# r10_0_328_1284.net
KiCad netlist of a schematic drawn in EAGLE
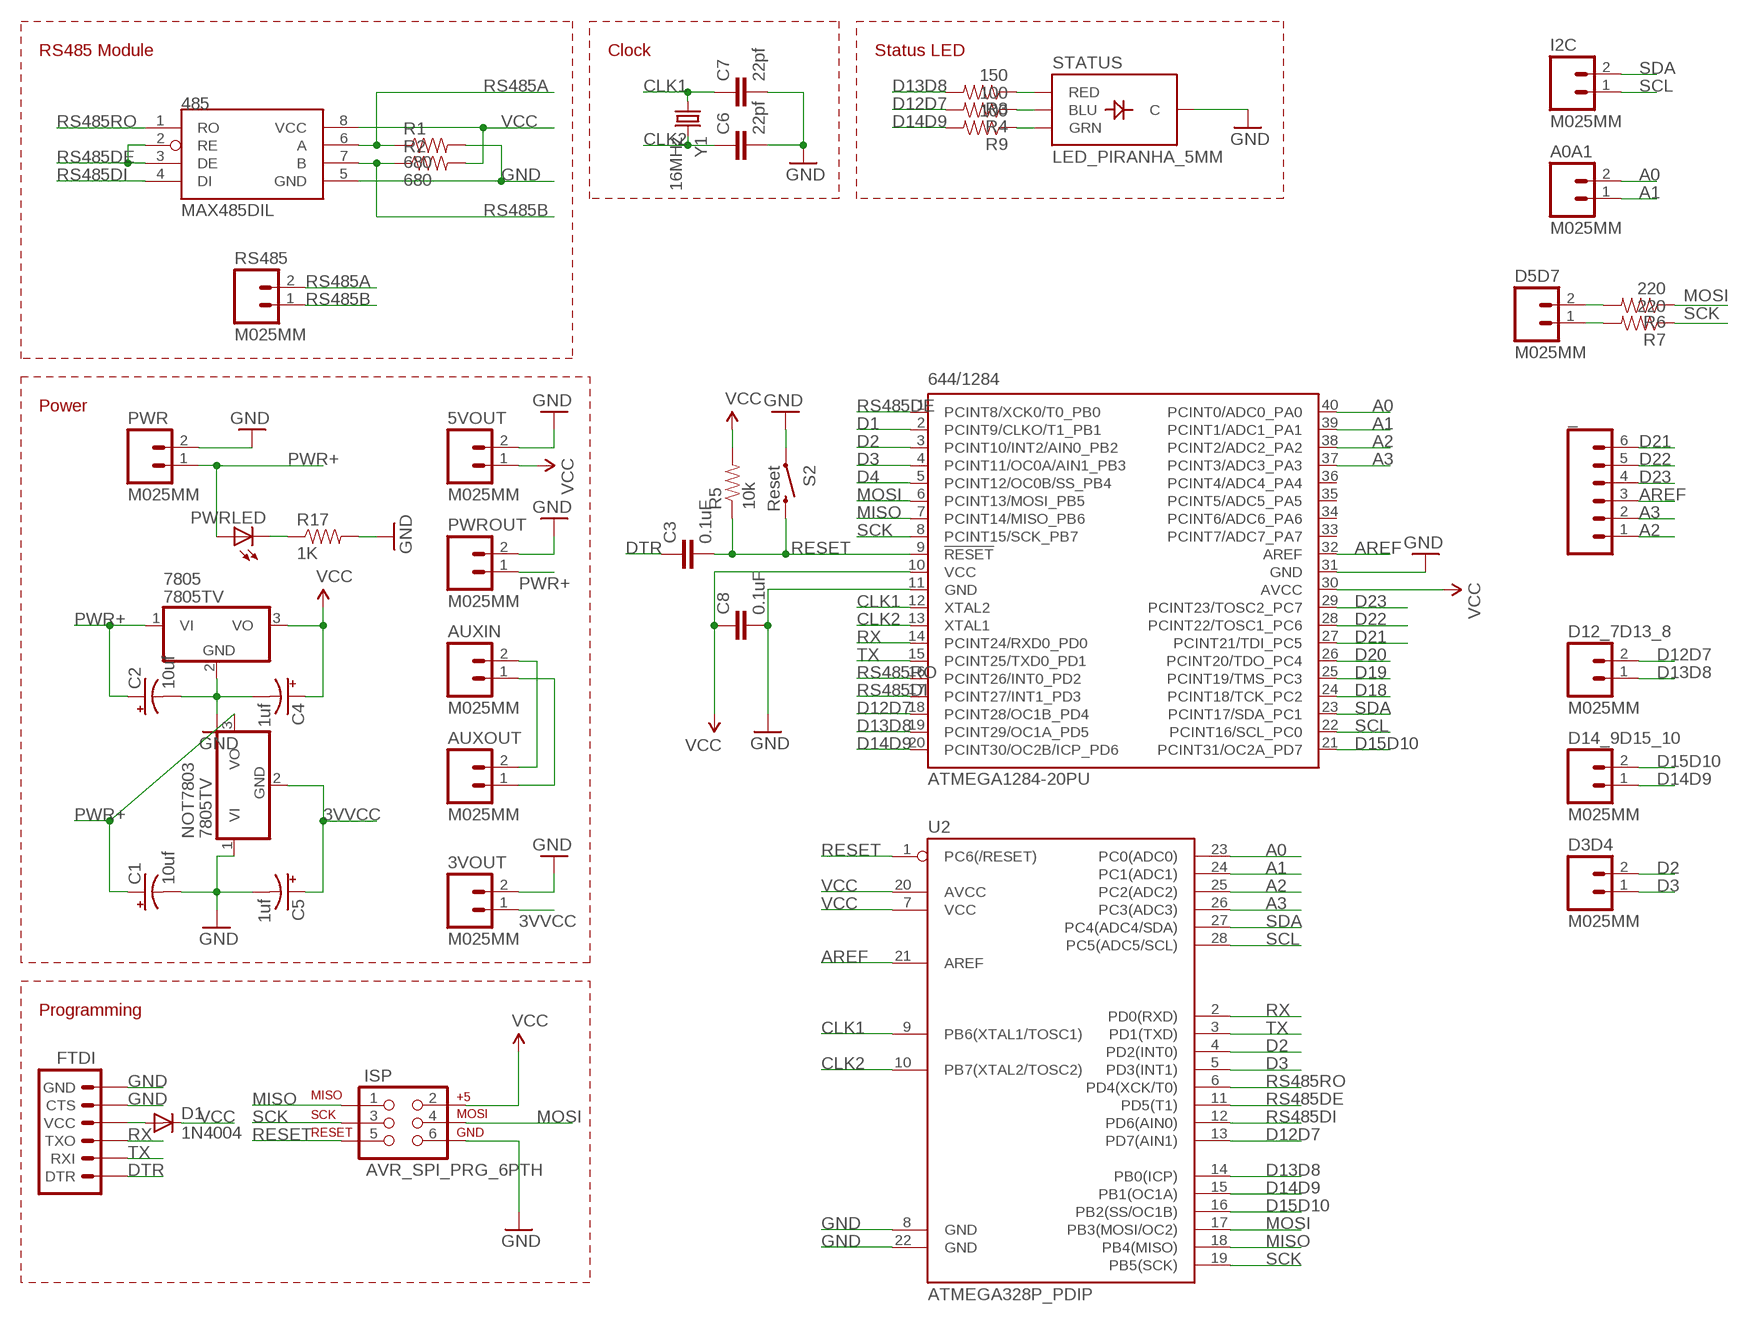
[diagram p0: schematic, sheet 1]

(export (version "E")
  (design (tool "Eeschema 10.0.6"))
  (components
    (comp (ref "3VOUT")
      (value "M025MM")
      (footprint "eagle-import:SCREWTERMINAL-5MM-2")
      (libsource (lib "eagle-import") (part "M025MM"))
    )
    (comp (ref "5VOUT")
      (value "M025MM")
      (footprint "eagle-import:SCREWTERMINAL-5MM-2")
      (libsource (lib "eagle-import") (part "M025MM"))
    )
    (comp (ref "485")
      (value "MAX485DIL")
      (footprint "eagle-import:DIL08")
      (libsource (lib "eagle-import") (part "MAX485DIL"))
    )
    (comp (ref "644/1284")
      (value "ATMEGA1284-20PU")
      (footprint "eagle-import:DIL40")
      (fields (field (name "MPN") "ATMEGA644-20PU"))
      (libsource (lib "eagle-import") (part "ATMEGA644-PU20"))
    )
    (comp (ref "7805")
      (value "7805TV")
      (footprint "eagle-import:TO220V")
      (libsource (lib "eagle-import") (part "78TV05"))
    )
    (comp (ref "A0A1")
      (value "M025MM")
      (footprint "eagle-import:SCREWTERMINAL-5MM-2")
      (libsource (lib "eagle-import") (part "M025MM"))
    )
    (comp (ref "AUXIN")
      (value "M025MM")
      (footprint "eagle-import:SCREWTERMINAL-5MM-2")
      (libsource (lib "eagle-import") (part "M025MM"))
    )
    (comp (ref "AUXOUT")
      (value "M025MM")
      (footprint "eagle-import:SCREWTERMINAL-5MM-2")
      (libsource (lib "eagle-import") (part "M025MM"))
    )
    (comp (ref "C1")
      (value "10uf")
      (footprint "eagle-import:CPOL-RADIAL-10UF-25V")
      (libsource (lib "eagle-import") (part "CAP_POLPTH2"))
    )
    (comp (ref "C2")
      (value "10uf")
      (footprint "eagle-import:CPOL-RADIAL-10UF-25V")
      (libsource (lib "eagle-import") (part "CAP_POLPTH2"))
    )
    (comp (ref "C3")
      (value "0.1uF")
      (footprint "eagle-import:CAP-PTH-SMALL")
      (libsource (lib "eagle-import") (part "CAPPTH"))
    )
    (comp (ref "C4")
      (value "1uf")
      (footprint "eagle-import:CPOL-RADIAL-10UF-25V")
      (libsource (lib "eagle-import") (part "CAP_POLPTH2"))
    )
    (comp (ref "C5")
      (value "1uf")
      (footprint "eagle-import:CPOL-RADIAL-10UF-25V")
      (libsource (lib "eagle-import") (part "CAP_POLPTH2"))
    )
    (comp (ref "C6")
      (value "22pf")
      (footprint "eagle-import:CAP-PTH-SMALL")
      (libsource (lib "eagle-import") (part "CAPPTH"))
    )
    (comp (ref "C7")
      (value "22pf")
      (footprint "eagle-import:CAP-PTH-SMALL")
      (libsource (lib "eagle-import") (part "CAPPTH"))
    )
    (comp (ref "C8")
      (value "0.1uF")
      (footprint "eagle-import:CAP-PTH-SMALL")
      (libsource (lib "eagle-import") (part "CAPPTH"))
    )
    (comp (ref "D1")
      (value "1N4004")
      (footprint "eagle-import:DO41-10")
      (libsource (lib "eagle-import") (part "1N4004"))
    )
    (comp (ref "D3D4")
      (value "M025MM")
      (footprint "eagle-import:SCREWTERMINAL-5MM-2")
      (libsource (lib "eagle-import") (part "M025MM"))
    )
    (comp (ref "D5D7")
      (value "M025MM")
      (footprint "eagle-import:SCREWTERMINAL-5MM-2")
      (libsource (lib "eagle-import") (part "M025MM"))
    )
    (comp (ref "D12_7D13_8")
      (value "M025MM")
      (footprint "eagle-import:SCREWTERMINAL-5MM-2")
      (libsource (lib "eagle-import") (part "M025MM"))
    )
    (comp (ref "D14_9D15_10")
      (value "M025MM")
      (footprint "eagle-import:SCREWTERMINAL-5MM-2")
      (libsource (lib "eagle-import") (part "M025MM"))
    )
    (comp (ref "FTDI")
      (value "ARDUINO_SERIAL_PROGRAMPTH")
      (footprint "eagle-import:1X06")
      (libsource (lib "eagle-import") (part "ARDUINO_SERIAL_PROGRAMPTH"))
    )
    (comp (ref "I2C")
      (value "M025MM")
      (footprint "eagle-import:SCREWTERMINAL-5MM-2")
      (libsource (lib "eagle-import") (part "M025MM"))
    )
    (comp (ref "ISP")
      (value "AVR_SPI_PRG_6PTH")
      (footprint "eagle-import:2X3")
      (libsource (lib "eagle-import") (part "AVR_SPI_PRG_6PTH"))
    )
    (comp (ref "NOT7803")
      (value "7805TV")
      (footprint "eagle-import:TO220V")
      (libsource (lib "eagle-import") (part "78TV05"))
    )
    (comp (ref "PWR")
      (value "M025MM")
      (footprint "eagle-import:SCREWTERMINAL-5MM-2")
      (libsource (lib "eagle-import") (part "M025MM"))
    )
    (comp (ref "PWRLED")
      (value "LED5MM")
      (footprint "eagle-import:LED5MM")
      (libsource (lib "eagle-import") (part "LED5MM"))
    )
    (comp (ref "PWROUT")
      (value "M025MM")
      (footprint "eagle-import:SCREWTERMINAL-5MM-2")
      (libsource (lib "eagle-import") (part "M025MM"))
    )
    (comp (ref "R1")
      (value "680")
      (footprint "eagle-import:AXIAL-0.4")
      (libsource (lib "eagle-import") (part "SparkFun-Resistors_RESISTORPTH-1/4W"))
    )
    (comp (ref "R2")
      (value "680")
      (footprint "eagle-import:AXIAL-0.4")
      (libsource (lib "eagle-import") (part "SparkFun-Resistors_RESISTORPTH-1/4W"))
    )
    (comp (ref "R3")
      (value "150")
      (footprint "eagle-import:AXIAL-0.4")
      (libsource (lib "eagle-import") (part "RESISTORPTH-1/4W"))
    )
    (comp (ref "R4")
      (value "100")
      (footprint "eagle-import:AXIAL-0.4")
      (libsource (lib "eagle-import") (part "RESISTORPTH-1/4W"))
    )
    (comp (ref "R5")
      (value "10k")
      (footprint "eagle-import:AXIAL-0.4")
      (libsource (lib "eagle-import") (part "RESISTORPTH-1/4W"))
    )
    (comp (ref "R6")
      (value "220")
      (footprint "eagle-import:AXIAL-0.4")
      (libsource (lib "eagle-import") (part "RESISTORPTH-1/4W"))
    )
    (comp (ref "R7")
      (value "220")
      (footprint "eagle-import:AXIAL-0.4")
      (libsource (lib "eagle-import") (part "RESISTORPTH-1/4W"))
    )
    (comp (ref "R9")
      (value "100")
      (footprint "eagle-import:AXIAL-0.4")
      (libsource (lib "eagle-import") (part "RESISTORPTH-1/4W"))
    )
    (comp (ref "R17")
      (value "1K")
      (footprint "eagle-import:AXIAL-0.4")
      (libsource (lib "eagle-import") (part "SparkFun-Resistors_RESISTORPTH-1/4W"))
    )
    (comp (ref "RS485")
      (value "M025MM")
      (footprint "eagle-import:SCREWTERMINAL-5MM-2")
      (libsource (lib "eagle-import") (part "M025MM"))
    )
    (comp (ref "S2")
      (value "Reset")
      (footprint "eagle-import:TACTILE_SWITCH_SMD")
      (libsource (lib "eagle-import") (part "SWITCH-MOMENTARY-2SMD"))
    )
    (comp (ref "STATUS")
      (value "LED_PIRANHA_5MM")
      (footprint "eagle-import:LED_PIRANHA_5MM")
      (libsource (lib "eagle-import") (part "LED_PIRANHA_5MM"))
    )
    (comp (ref "U2")
      (value "ATMEGA328P_PDIP")
      (footprint "eagle-import:DIL28-3")
      (libsource (lib "eagle-import") (part "ATMEGA328P_PDIP"))
    )
    (comp (ref "Y1")
      (value "16MHz")
      (footprint "eagle-import:HC49US")
      (libsource (lib "eagle-import") (part "CRYSTALHC49US"))
    )
    (comp (ref "_")
      (value "M06NO_SILK")
      (footprint "eagle-import:1X06_NO_SILK")
      (libsource (lib "eagle-import") (part "M06NO_SILK"))
    )
  )
  (nets
    (net (code "1") (name "/3VVCC") (class "Default")
      (node (ref "3VOUT") (pin "1") (pinfunction "1_1") (pintype "passive"))
      (node (ref "C5") (pin "1") (pinfunction "+_1") (pintype "passive"))
      (node (ref "NOT7803") (pin "2") (pinfunction "GND_2") (pintype "passive"))
    )
    (net (code "2") (name "/A0") (class "Default")
      (node (ref "644/1284") (pin "40") (pinfunction "PCINT0/ADC0_PA0_40") (pintype "bidirectional"))
      (node (ref "A0A1") (pin "2") (pinfunction "2_2") (pintype "passive"))
      (node (ref "U2") (pin "23") (pinfunction "PC0(ADC0)_23") (pintype "bidirectional"))
    )
    (net (code "3") (name "/A1") (class "Default")
      (node (ref "644/1284") (pin "39") (pinfunction "PCINT1/ADC1_PA1_39") (pintype "bidirectional"))
      (node (ref "A0A1") (pin "1") (pinfunction "1_1") (pintype "passive"))
      (node (ref "U2") (pin "24") (pinfunction "PC1(ADC1)_24") (pintype "bidirectional"))
    )
    (net (code "4") (name "/A2") (class "Default")
      (node (ref "644/1284") (pin "38") (pinfunction "PCINT2/ADC2_PA2_38") (pintype "bidirectional"))
      (node (ref "U2") (pin "25") (pinfunction "PC2(ADC2)_25") (pintype "bidirectional"))
      (node (ref "_") (pin "1") (pinfunction "1_1") (pintype "passive"))
    )
    (net (code "5") (name "/A3") (class "Default")
      (node (ref "644/1284") (pin "37") (pinfunction "PCINT3/ADC3_PA3_37") (pintype "bidirectional"))
      (node (ref "U2") (pin "26") (pinfunction "PC3(ADC3)_26") (pintype "bidirectional"))
      (node (ref "_") (pin "2") (pinfunction "2_2") (pintype "passive"))
    )
    (net (code "6") (name "/AREF") (class "Default")
      (node (ref "644/1284") (pin "32") (pinfunction "AREF_32") (pintype "passive"))
      (node (ref "U2") (pin "21") (pinfunction "AREF_21") (pintype "bidirectional"))
      (node (ref "_") (pin "3") (pinfunction "3_3") (pintype "passive"))
    )
    (net (code "7") (name "/CLK1") (class "Default")
      (node (ref "644/1284") (pin "12") (pinfunction "XTAL2_12") (pintype "output"))
      (node (ref "C7") (pin "1") (pinfunction "1_1") (pintype "passive"))
      (node (ref "U2") (pin "9") (pinfunction "PB6(XTAL1/TOSC1)_9") (pintype "bidirectional"))
      (node (ref "Y1") (pin "1") (pinfunction "1_1") (pintype "passive"))
    )
    (net (code "8") (name "/CLK2") (class "Default")
      (node (ref "644/1284") (pin "13") (pinfunction "XTAL1_13") (pintype "input"))
      (node (ref "C6") (pin "1") (pinfunction "1_1") (pintype "passive"))
      (node (ref "U2") (pin "10") (pinfunction "PB7(XTAL2/TOSC2)_10") (pintype "bidirectional"))
      (node (ref "Y1") (pin "2") (pinfunction "2_2") (pintype "passive"))
    )
    (net (code "9") (name "/D1") (class "Default")
      (node (ref "644/1284") (pin "2") (pinfunction "PCINT9/CLKO/T1_PB1_2") (pintype "bidirectional"))
    )
    (net (code "10") (name "/D2") (class "Default")
      (node (ref "644/1284") (pin "3") (pinfunction "PCINT10/INT2/AIN0_PB2_3") (pintype "bidirectional"))
      (node (ref "D3D4") (pin "2") (pinfunction "2_2") (pintype "passive"))
      (node (ref "U2") (pin "4") (pinfunction "PD2(INT0)_4") (pintype "bidirectional"))
    )
    (net (code "11") (name "/D3") (class "Default")
      (node (ref "644/1284") (pin "4") (pinfunction "PCINT11/OC0A/AIN1_PB3_4") (pintype "bidirectional"))
      (node (ref "D3D4") (pin "1") (pinfunction "1_1") (pintype "passive"))
      (node (ref "U2") (pin "5") (pinfunction "PD3(INT1)_5") (pintype "bidirectional"))
    )
    (net (code "12") (name "/D4") (class "Default")
      (node (ref "644/1284") (pin "5") (pinfunction "PCINT12/OC0B/SS_PB4_5") (pintype "bidirectional"))
    )
    (net (code "13") (name "/D12D7") (class "Default")
      (node (ref "644/1284") (pin "18") (pinfunction "PCINT28/OC1B_PD4_18") (pintype "bidirectional"))
      (node (ref "D12_7D13_8") (pin "2") (pinfunction "2_2") (pintype "passive"))
      (node (ref "R4") (pin "P$2") (pinfunction "2_P$2") (pintype "passive"))
      (node (ref "U2") (pin "13") (pinfunction "PD7(AIN1)_13") (pintype "bidirectional"))
    )
    (net (code "14") (name "/D13D8") (class "Default")
      (node (ref "644/1284") (pin "19") (pinfunction "PCINT29/OC1A_PD5_19") (pintype "bidirectional"))
      (node (ref "D12_7D13_8") (pin "1") (pinfunction "1_1") (pintype "passive"))
      (node (ref "R3") (pin "P$2") (pinfunction "2_P$2") (pintype "passive"))
      (node (ref "U2") (pin "14") (pinfunction "PB0(ICP)_14") (pintype "bidirectional"))
    )
    (net (code "15") (name "/D14D9") (class "Default")
      (node (ref "644/1284") (pin "20") (pinfunction "PCINT30/OC2B/ICP_PD6_20") (pintype "bidirectional"))
      (node (ref "D14_9D15_10") (pin "1") (pinfunction "1_1") (pintype "passive"))
      (node (ref "R9") (pin "P$2") (pinfunction "2_P$2") (pintype "passive"))
      (node (ref "U2") (pin "15") (pinfunction "PB1(OC1A)_15") (pintype "bidirectional"))
    )
    (net (code "16") (name "/D15D10") (class "Default")
      (node (ref "644/1284") (pin "21") (pinfunction "PCINT31/OC2A_PD7_21") (pintype "bidirectional"))
      (node (ref "D14_9D15_10") (pin "2") (pinfunction "2_2") (pintype "passive"))
      (node (ref "U2") (pin "16") (pinfunction "PB2(SS/OC1B)_16") (pintype "bidirectional"))
    )
    (net (code "17") (name "/D18") (class "Default")
      (node (ref "644/1284") (pin "24") (pinfunction "PCINT18/TCK_PC2_24") (pintype "bidirectional"))
    )
    (net (code "18") (name "/D19") (class "Default")
      (node (ref "644/1284") (pin "25") (pinfunction "PCINT19/TMS_PC3_25") (pintype "bidirectional"))
    )
    (net (code "19") (name "/D20") (class "Default")
      (node (ref "644/1284") (pin "26") (pinfunction "PCINT20/TDO_PC4_26") (pintype "bidirectional"))
    )
    (net (code "20") (name "/D21") (class "Default")
      (node (ref "644/1284") (pin "27") (pinfunction "PCINT21/TDI_PC5_27") (pintype "bidirectional"))
      (node (ref "_") (pin "6") (pinfunction "6_6") (pintype "passive"))
    )
    (net (code "21") (name "/D22") (class "Default")
      (node (ref "644/1284") (pin "28") (pinfunction "PCINT22/TOSC1_PC6_28") (pintype "bidirectional"))
      (node (ref "_") (pin "5") (pinfunction "5_5") (pintype "passive"))
    )
    (net (code "22") (name "/D23") (class "Default")
      (node (ref "644/1284") (pin "29") (pinfunction "PCINT23/TOSC2_PC7_29") (pintype "bidirectional"))
      (node (ref "_") (pin "4") (pinfunction "4_4") (pintype "passive"))
    )
    (net (code "23") (name "/DTR") (class "Default")
      (node (ref "C3") (pin "1") (pinfunction "1_1") (pintype "passive"))
      (node (ref "FTDI") (pin "DTR") (pinfunction "DTR_DTR") (pintype "passive"))
    )
    (net (code "24") (name "/MISO") (class "Default")
      (node (ref "644/1284") (pin "7") (pinfunction "PCINT14/MISO_PB6_7") (pintype "bidirectional"))
      (node (ref "ISP") (pin "1") (pinfunction "1_1") (pintype "passive"))
      (node (ref "U2") (pin "18") (pinfunction "PB4(MISO)_18") (pintype "bidirectional"))
    )
    (net (code "25") (name "/MOSI") (class "Default")
      (node (ref "644/1284") (pin "6") (pinfunction "PCINT13/MOSI_PB5_6") (pintype "bidirectional"))
      (node (ref "ISP") (pin "4") (pinfunction "4_4") (pintype "passive"))
      (node (ref "R6") (pin "P$1") (pinfunction "1_P$1") (pintype "passive"))
      (node (ref "U2") (pin "17") (pinfunction "PB3(MOSI/OC2)_17") (pintype "bidirectional"))
    )
    (net (code "26") (name "/PWR+") (class "Default")
      (node (ref "7805") (pin "1") (pinfunction "VI_1") (pintype "input"))
      (node (ref "C1") (pin "1") (pinfunction "+_1") (pintype "passive"))
      (node (ref "C2") (pin "1") (pinfunction "+_1") (pintype "passive"))
      (node (ref "NOT7803") (pin "3") (pinfunction "VO_3") (pintype "passive"))
      (node (ref "PWR") (pin "1") (pinfunction "1_1") (pintype "passive"))
      (node (ref "PWRLED") (pin "A") (pinfunction "A_A") (pintype "passive"))
      (node (ref "PWROUT") (pin "1") (pinfunction "1_1") (pintype "passive"))
    )
    (net (code "27") (name "/RESET") (class "Default")
      (node (ref "644/1284") (pin "9") (pinfunction "~{RESET}_9") (pintype "input"))
      (node (ref "C3") (pin "2") (pinfunction "2_2") (pintype "passive"))
      (node (ref "ISP") (pin "5") (pinfunction "5_5") (pintype "passive"))
      (node (ref "R5") (pin "P$1") (pinfunction "1_P$1") (pintype "passive"))
      (node (ref "S2") (pin "3") (pinfunction "2_3") (pintype "passive"))
      (node (ref "U2") (pin "1") (pinfunction "PC6(/RESET)_1") (pintype "bidirectional"))
    )
    (net (code "28") (name "/RS485A") (class "Default")
      (node (ref "485") (pin "6") (pinfunction "A_6") (pintype "bidirectional"))
      (node (ref "R1") (pin "P$1") (pinfunction "1_P$1") (pintype "passive"))
      (node (ref "RS485") (pin "2") (pinfunction "2_2") (pintype "passive"))
    )
    (net (code "29") (name "/RS485B") (class "Default")
      (node (ref "485") (pin "7") (pinfunction "B_7") (pintype "bidirectional"))
      (node (ref "R2") (pin "P$1") (pinfunction "1_P$1") (pintype "passive"))
      (node (ref "RS485") (pin "1") (pinfunction "1_1") (pintype "passive"))
    )
    (net (code "30") (name "/RS485DE") (class "Default")
      (node (ref "485") (pin "2") (pinfunction "RE_2") (pintype "bidirectional"))
      (node (ref "485") (pin "3") (pinfunction "DE_3") (pintype "bidirectional"))
      (node (ref "644/1284") (pin "1") (pinfunction "PCINT8/XCK0/T0_PB0_1") (pintype "bidirectional"))
      (node (ref "U2") (pin "11") (pinfunction "PD5(T1)_11") (pintype "bidirectional"))
    )
    (net (code "31") (name "/RS485DI") (class "Default")
      (node (ref "485") (pin "4") (pinfunction "DI_4") (pintype "bidirectional"))
      (node (ref "644/1284") (pin "17") (pinfunction "PCINT27/INT1_PD3_17") (pintype "bidirectional"))
      (node (ref "U2") (pin "12") (pinfunction "PD6(AIN0)_12") (pintype "bidirectional"))
    )
    (net (code "32") (name "/RS485RO") (class "Default")
      (node (ref "485") (pin "1") (pinfunction "RO_1") (pintype "bidirectional"))
      (node (ref "644/1284") (pin "16") (pinfunction "PCINT26/INT0_PD2_16") (pintype "bidirectional"))
      (node (ref "U2") (pin "6") (pinfunction "PD4(XCK/T0)_6") (pintype "bidirectional"))
    )
    (net (code "33") (name "/RX") (class "Default")
      (node (ref "644/1284") (pin "14") (pinfunction "PCINT24/RXD0_PD0_14") (pintype "bidirectional"))
      (node (ref "FTDI") (pin "TXO") (pinfunction "TXO_TXO") (pintype "passive"))
      (node (ref "U2") (pin "2") (pinfunction "PD0(RXD)_2") (pintype "bidirectional"))
    )
    (net (code "34") (name "/SCK") (class "Default")
      (node (ref "644/1284") (pin "8") (pinfunction "PCINT15/SCK_PB7_8") (pintype "bidirectional"))
      (node (ref "ISP") (pin "3") (pinfunction "3_3") (pintype "passive"))
      (node (ref "R7") (pin "P$1") (pinfunction "1_P$1") (pintype "passive"))
      (node (ref "U2") (pin "19") (pinfunction "PB5(SCK)_19") (pintype "bidirectional"))
    )
    (net (code "35") (name "/SCL") (class "Default")
      (node (ref "644/1284") (pin "22") (pinfunction "PCINT16/SCL_PC0_22") (pintype "bidirectional"))
      (node (ref "I2C") (pin "1") (pinfunction "1_1") (pintype "passive"))
      (node (ref "U2") (pin "28") (pinfunction "PC5(ADC5/SCL)_28") (pintype "bidirectional"))
    )
    (net (code "36") (name "/SDA") (class "Default")
      (node (ref "644/1284") (pin "23") (pinfunction "PCINT17/SDA_PC1_23") (pintype "bidirectional"))
      (node (ref "I2C") (pin "2") (pinfunction "2_2") (pintype "passive"))
      (node (ref "U2") (pin "27") (pinfunction "PC4(ADC4/SDA)_27") (pintype "bidirectional"))
    )
    (net (code "37") (name "/TX") (class "Default")
      (node (ref "644/1284") (pin "15") (pinfunction "PCINT25/TXD0_PD1_15") (pintype "bidirectional"))
      (node (ref "FTDI") (pin "RXI") (pinfunction "RXI_RXI") (pintype "passive"))
      (node (ref "U2") (pin "3") (pinfunction "PD1(TXD)_3") (pintype "bidirectional"))
    )
    (net (code "38") (name "GND") (class "Default")
      (node (ref "3VOUT") (pin "2") (pinfunction "2_2") (pintype "passive"))
      (node (ref "485") (pin "5") (pinfunction "GND_5") (pintype "bidirectional"))
      (node (ref "5VOUT") (pin "2") (pinfunction "2_2") (pintype "passive"))
      (node (ref "644/1284") (pin "11") (pinfunction "GND_11") (pintype "power_in"))
      (node (ref "644/1284") (pin "31") (pinfunction "GND_31") (pintype "power_in"))
      (node (ref "7805") (pin "2") (pinfunction "GND_2") (pintype "passive"))
      (node (ref "C1") (pin "2") (pinfunction "-_2") (pintype "passive"))
      (node (ref "C2") (pin "2") (pinfunction "-_2") (pintype "passive"))
      (node (ref "C4") (pin "2") (pinfunction "-_2") (pintype "passive"))
      (node (ref "C5") (pin "2") (pinfunction "-_2") (pintype "passive"))
      (node (ref "C6") (pin "2") (pinfunction "2_2") (pintype "passive"))
      (node (ref "C7") (pin "2") (pinfunction "2_2") (pintype "passive"))
      (node (ref "C8") (pin "2") (pinfunction "2_2") (pintype "passive"))
      (node (ref "FTDI") (pin "CTS") (pinfunction "CTS_CTS") (pintype "passive"))
      (node (ref "FTDI") (pin "GND") (pinfunction "GND_GND") (pintype "passive"))
      (node (ref "ISP") (pin "6") (pinfunction "6_6") (pintype "passive"))
      (node (ref "NOT7803") (pin "1") (pinfunction "VI_1") (pintype "input"))
      (node (ref "PWR") (pin "2") (pinfunction "2_2") (pintype "passive"))
      (node (ref "PWROUT") (pin "2") (pinfunction "2_2") (pintype "passive"))
      (node (ref "R1") (pin "P$2") (pinfunction "2_P$2") (pintype "passive"))
      (node (ref "R17") (pin "P$2") (pinfunction "2_P$2") (pintype "passive"))
      (node (ref "S2") (pin "1") (pinfunction "1_1") (pintype "passive"))
      (node (ref "STATUS") (pin "-") (pinfunction "C_-") (pintype "bidirectional"))
      (node (ref "U2") (pin "22") (pinfunction "GND_22") (pintype "bidirectional"))
      (node (ref "U2") (pin "8") (pinfunction "GND_8") (pintype "bidirectional"))
    )
    (net (code "39") (name "Net-(AUXIN-Pad1)") (class "Default")
      (node (ref "AUXIN") (pin "1") (pinfunction "1_1") (pintype "passive"))
      (node (ref "AUXOUT") (pin "1") (pinfunction "1_1") (pintype "passive"))
    )
    (net (code "40") (name "Net-(AUXIN-Pad2)") (class "Default")
      (node (ref "AUXIN") (pin "2") (pinfunction "2_2") (pintype "passive"))
      (node (ref "AUXOUT") (pin "2") (pinfunction "2_2") (pintype "passive"))
    )
    (net (code "41") (name "Net-(D1-PadA)") (class "Default")
      (node (ref "D1") (pin "A") (pinfunction "A_A") (pintype "passive"))
      (node (ref "FTDI") (pin "VCC") (pinfunction "VCC_VCC") (pintype "passive"))
    )
    (net (code "42") (name "Net-(PWRLED-C)") (class "Default")
      (node (ref "PWRLED") (pin "K") (pinfunction "C_K") (pintype "passive"))
      (node (ref "R17") (pin "P$1") (pinfunction "1_P$1") (pintype "passive"))
    )
    (net (code "43") (name "Net-(R3-1)") (class "Default")
      (node (ref "R3") (pin "P$1") (pinfunction "1_P$1") (pintype "passive"))
      (node (ref "STATUS") (pin "R") (pinfunction "RED_R") (pintype "bidirectional"))
    )
    (net (code "44") (name "Net-(R4-1)") (class "Default")
      (node (ref "R4") (pin "P$1") (pinfunction "1_P$1") (pintype "passive"))
      (node (ref "STATUS") (pin "B") (pinfunction "BLU_B") (pintype "bidirectional"))
    )
    (net (code "45") (name "Net-(R6-2)") (class "Default")
      (node (ref "D5D7") (pin "2") (pinfunction "2_2") (pintype "passive"))
      (node (ref "R6") (pin "P$2") (pinfunction "2_P$2") (pintype "passive"))
    )
    (net (code "46") (name "Net-(R7-2)") (class "Default")
      (node (ref "D5D7") (pin "1") (pinfunction "1_1") (pintype "passive"))
      (node (ref "R7") (pin "P$2") (pinfunction "2_P$2") (pintype "passive"))
    )
    (net (code "47") (name "Net-(R9-1)") (class "Default")
      (node (ref "R9") (pin "P$1") (pinfunction "1_P$1") (pintype "passive"))
      (node (ref "STATUS") (pin "G") (pinfunction "GRN_G") (pintype "bidirectional"))
    )
    (net (code "48") (name "VCC") (class "Default")
      (node (ref "485") (pin "8") (pinfunction "VCC_8") (pintype "bidirectional"))
      (node (ref "5VOUT") (pin "1") (pinfunction "1_1") (pintype "passive"))
      (node (ref "644/1284") (pin "10") (pinfunction "VCC_10") (pintype "power_in"))
      (node (ref "644/1284") (pin "30") (pinfunction "AVCC_30") (pintype "power_in"))
      (node (ref "7805") (pin "3") (pinfunction "VO_3") (pintype "passive"))
      (node (ref "C4") (pin "1") (pinfunction "+_1") (pintype "passive"))
      (node (ref "C8") (pin "1") (pinfunction "1_1") (pintype "passive"))
      (node (ref "D1") (pin "C") (pinfunction "C_C") (pintype "passive"))
      (node (ref "ISP") (pin "2") (pinfunction "2_2") (pintype "passive"))
      (node (ref "R2") (pin "P$2") (pinfunction "2_P$2") (pintype "passive"))
      (node (ref "R5") (pin "P$2") (pinfunction "2_P$2") (pintype "passive"))
      (node (ref "U2") (pin "20") (pinfunction "AVCC_20") (pintype "bidirectional"))
      (node (ref "U2") (pin "7") (pinfunction "VCC_7") (pintype "bidirectional"))
    )
    (net (code "49") (name "unconnected-(644/1284-PCINT4{slash}ADC4_PA4-Pad36)") (class "Default")
      (node (ref "644/1284") (pin "36") (pinfunction "PCINT4/ADC4_PA4_36") (pintype "bidirectional"))
    )
    (net (code "50") (name "unconnected-(644/1284-PCINT5{slash}ADC5_PA5-Pad35)") (class "Default")
      (node (ref "644/1284") (pin "35") (pinfunction "PCINT5/ADC5_PA5_35") (pintype "bidirectional"))
    )
    (net (code "51") (name "unconnected-(644/1284-PCINT6{slash}ADC6_PA6-Pad34)") (class "Default")
      (node (ref "644/1284") (pin "34") (pinfunction "PCINT6/ADC6_PA6_34") (pintype "bidirectional"))
    )
    (net (code "52") (name "unconnected-(644/1284-PCINT7{slash}ADC7_PA7-Pad33)") (class "Default")
      (node (ref "644/1284") (pin "33") (pinfunction "PCINT7/ADC7_PA7_33") (pintype "bidirectional"))
    )
  )
)
